# board_schematic_v2.net
KiCad netlist of a schematic drawn in EAGLE
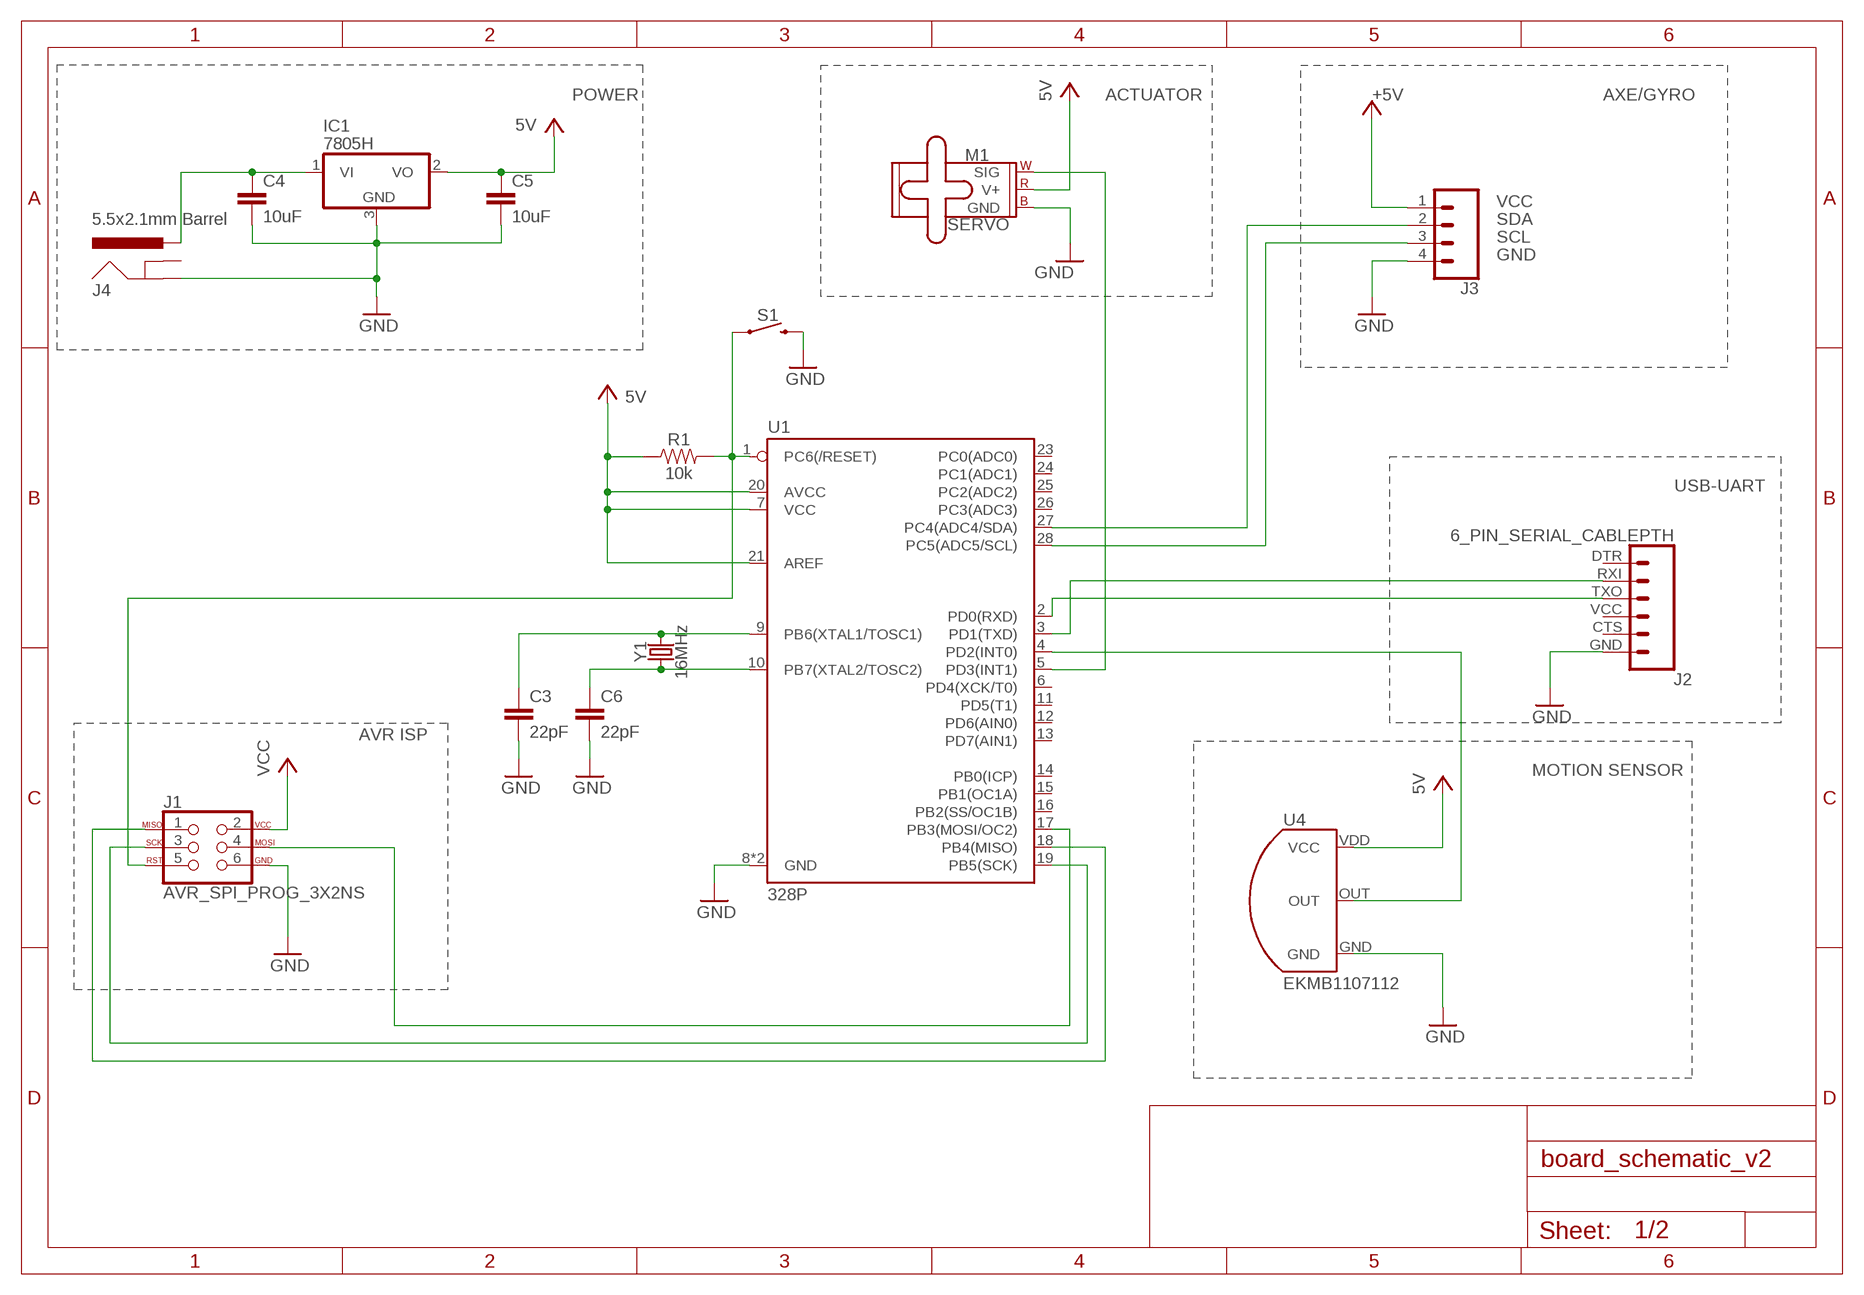
[diagram p0: schematic, sheet 1]

(export (version "E")
  (design (tool "Eeschema 10.0.6"))
  (components
    (comp (ref "C3")
      (value "22pF")
      (footprint "eagle-import:0402-TIGHT")
      (libsource (lib "eagle-import") (part "22PF-0402T-16V-10%"))
    )
    (comp (ref "C4")
      (value "10uF")
      (footprint "eagle-import:0402-TIGHT")
      (libsource (lib "eagle-import") (part "10UF-0402T-6.3V-20%"))
    )
    (comp (ref "C5")
      (value "10uF")
      (footprint "eagle-import:0402-TIGHT")
      (libsource (lib "eagle-import") (part "10UF-0402T-6.3V-20%"))
    )
    (comp (ref "C6")
      (value "22pF")
      (footprint "eagle-import:0402-TIGHT")
      (libsource (lib "eagle-import") (part "22PF-0402T-16V-10%"))
    )
    (comp (ref "IC1")
      (value "7805H")
      (footprint "eagle-import:TO39")
      (libsource (lib "eagle-import") (part "78H05"))
    )
    (comp (ref "J1")
      (value "AVR_SPI_PROG_3X2NS")
      (footprint "eagle-import:2X3-NS")
      (libsource (lib "eagle-import") (part "AVR_SPI_PROG_3X2NS"))
    )
    (comp (ref "J2")
      (value "6_PIN_SERIAL_CABLEPTH")
      (footprint "eagle-import:FTDI_BASIC")
      (libsource (lib "eagle-import") (part "6_PIN_SERIAL_CABLEPTH"))
    )
    (comp (ref "J3")
      (value "CONN_04PTH")
      (footprint "eagle-import:1X04")
      (libsource (lib "eagle-import") (part "CONN_04PTH"))
    )
    (comp (ref "J4")
      (value "5.5x2.1mm Barrel")
      (footprint "eagle-import:POWER_JACK_SMD")
      (libsource (lib "eagle-import") (part "POWER_JACKSMD"))
    )
    (comp (ref "M1")
      (value "SERVO")
      (footprint "eagle-import:1X03")
      (libsource (lib "eagle-import") (part "SERVO"))
    )
    (comp (ref "R1")
      (value "10k")
      (footprint "eagle-import:0402")
      (libsource (lib "eagle-import") (part "10KOHM-0402-1/16W-1%"))
    )
    (comp (ref "S1")
      (value "MOMENTARY-SWITCH-SPST-PTH-6.0MM")
      (footprint "eagle-import:TACTILE_SWITCH_PTH_6.0MM")
      (libsource (lib "eagle-import") (part "MOMENTARY-SWITCH-SPST-PTH-6.0MM"))
    )
    (comp (ref "U1")
      (value "328P")
      (footprint "eagle-import:DIP28")
      (libsource (lib "eagle-import") (part "ATMEGA328P_PDIP"))
    )
    (comp (ref "U4")
      (value "EKMB1107112")
      (footprint "eagle-import:TO-3")
      (libsource (lib "eagle-import") (part "PIR_EKMB1107112"))
    )
    (comp (ref "Y1")
      (value "16MHz")
      (footprint "eagle-import:HC49US")
      (libsource (lib "eagle-import") (part "CRYSTAL-16MHZPTH-HC49US"))
    )
  )
  (nets
    (net (code "1") (name "GND") (class "Default")
      (node (ref "C3") (pin "2") (pinfunction "2_2") (pintype "passive"))
      (node (ref "C4") (pin "2") (pinfunction "2_2") (pintype "passive"))
      (node (ref "C5") (pin "2") (pinfunction "2_2") (pintype "passive"))
      (node (ref "C6") (pin "2") (pinfunction "2_2") (pintype "passive"))
      (node (ref "IC1") (pin "3") (pinfunction "GND_3") (pintype "passive"))
      (node (ref "J1") (pin "6") (pinfunction "6_6") (pintype "passive"))
      (node (ref "J2") (pin "GND") (pinfunction "6_GND") (pintype "passive"))
      (node (ref "J3") (pin "4") (pinfunction "4_4") (pintype "passive"))
      (node (ref "J4") (pin "P$4") (pinfunction "GND_P$4") (pintype "bidirectional"))
      (node (ref "M1") (pin "3") (pinfunction "GND_3") (pintype "bidirectional"))
      (node (ref "S1") (pin "3") (pinfunction "2_3") (pintype "passive"))
      (node (ref "U1") (pin "22") (pinfunction "GND_22") (pintype "bidirectional"))
      (node (ref "U1") (pin "8") (pinfunction "GND_8") (pintype "bidirectional"))
      (node (ref "U4") (pin "GND") (pinfunction "GND_GND") (pintype "bidirectional"))
    )
    (net (code "2") (name "Net-(IC1-VI)") (class "Default")
      (node (ref "C4") (pin "1") (pinfunction "1_1") (pintype "passive"))
      (node (ref "IC1") (pin "1") (pinfunction "VI_1") (pintype "input"))
      (node (ref "J4") (pin "VIN0") (pinfunction "PWR_VIN0") (pintype "bidirectional"))
    )
    (net (code "3") (name "Net-(J2-2)") (class "Default")
      (node (ref "J2") (pin "RXI") (pinfunction "2_RXI") (pintype "passive"))
      (node (ref "U1") (pin "3") (pinfunction "PD1(TXD)_3") (pintype "bidirectional"))
    )
    (net (code "4") (name "Net-(J2-3)") (class "Default")
      (node (ref "J2") (pin "TXO") (pinfunction "3_TXO") (pintype "passive"))
      (node (ref "U1") (pin "2") (pinfunction "PD0(RXD)_2") (pintype "bidirectional"))
    )
    (net (code "5") (name "Net-(M1-SIG)") (class "Default")
      (node (ref "M1") (pin "1") (pinfunction "SIG_1") (pintype "bidirectional"))
      (node (ref "U1") (pin "5") (pinfunction "PD3(INT1)_5") (pintype "bidirectional"))
    )
    (net (code "6") (name "Net-(U1-PB3(MOSI{slash}OC2))") (class "Default")
      (node (ref "J1") (pin "4") (pinfunction "4_4") (pintype "passive"))
      (node (ref "U1") (pin "17") (pinfunction "PB3(MOSI/OC2)_17") (pintype "bidirectional"))
    )
    (net (code "7") (name "Net-(U1-PB4(MISO))") (class "Default")
      (node (ref "J1") (pin "1") (pinfunction "1_1") (pintype "passive"))
      (node (ref "U1") (pin "18") (pinfunction "PB4(MISO)_18") (pintype "bidirectional"))
    )
    (net (code "8") (name "Net-(U1-PB5(SCK))") (class "Default")
      (node (ref "J1") (pin "3") (pinfunction "3_3") (pintype "passive"))
      (node (ref "U1") (pin "19") (pinfunction "PB5(SCK)_19") (pintype "bidirectional"))
    )
    (net (code "9") (name "Net-(U1-PB6(XTAL1{slash}TOSC1))") (class "Default")
      (node (ref "C3") (pin "1") (pinfunction "1_1") (pintype "passive"))
      (node (ref "U1") (pin "9") (pinfunction "PB6(XTAL1/TOSC1)_9") (pintype "bidirectional"))
      (node (ref "Y1") (pin "2") (pinfunction "2_2") (pintype "passive"))
    )
    (net (code "10") (name "Net-(U1-PB7(XTAL2{slash}TOSC2))") (class "Default")
      (node (ref "C6") (pin "1") (pinfunction "1_1") (pintype "passive"))
      (node (ref "U1") (pin "10") (pinfunction "PB7(XTAL2/TOSC2)_10") (pintype "bidirectional"))
      (node (ref "Y1") (pin "1") (pinfunction "1_1") (pintype "passive"))
    )
    (net (code "11") (name "Net-(U1-PC4(ADC4{slash}SDA))") (class "Default")
      (node (ref "J3") (pin "2") (pinfunction "2_2") (pintype "passive"))
      (node (ref "U1") (pin "27") (pinfunction "PC4(ADC4/SDA)_27") (pintype "bidirectional"))
    )
    (net (code "12") (name "Net-(U1-PC5(ADC5{slash}SCL))") (class "Default")
      (node (ref "J3") (pin "3") (pinfunction "3_3") (pintype "passive"))
      (node (ref "U1") (pin "28") (pinfunction "PC5(ADC5/SCL)_28") (pintype "bidirectional"))
    )
    (net (code "13") (name "Net-(U1-PC6({slash}RESET))") (class "Default")
      (node (ref "J1") (pin "5") (pinfunction "5_5") (pintype "passive"))
      (node (ref "R1") (pin "2") (pinfunction "2_2") (pintype "passive"))
      (node (ref "S1") (pin "1") (pinfunction "1_1") (pintype "passive"))
      (node (ref "U1") (pin "1") (pinfunction "PC6(/RESET)_1") (pintype "bidirectional"))
    )
    (net (code "14") (name "Net-(U1-PD2(INT0))") (class "Default")
      (node (ref "U1") (pin "4") (pinfunction "PD2(INT0)_4") (pintype "bidirectional"))
      (node (ref "U4") (pin "OUT") (pinfunction "OUT_OUT") (pintype "bidirectional"))
    )
    (net (code "15") (name "VCC") (class "Default")
      (node (ref "C5") (pin "1") (pinfunction "1_1") (pintype "passive"))
      (node (ref "IC1") (pin "2") (pinfunction "VO_2") (pintype "passive"))
      (node (ref "J1") (pin "2") (pinfunction "2_2") (pintype "passive"))
      (node (ref "J3") (pin "1") (pinfunction "1_1") (pintype "passive"))
      (node (ref "M1") (pin "2") (pinfunction "V+_2") (pintype "bidirectional"))
      (node (ref "R1") (pin "1") (pinfunction "1_1") (pintype "passive"))
      (node (ref "U1") (pin "20") (pinfunction "AVCC_20") (pintype "bidirectional"))
      (node (ref "U1") (pin "21") (pinfunction "AREF_21") (pintype "bidirectional"))
      (node (ref "U1") (pin "7") (pinfunction "VCC_7") (pintype "bidirectional"))
      (node (ref "U4") (pin "VDD") (pinfunction "VCC_VDD") (pintype "bidirectional"))
    )
    (net (code "16") (name "unconnected-(J2-1-PadDTR)") (class "Default")
      (node (ref "J2") (pin "DTR") (pinfunction "1_DTR") (pintype "passive"))
    )
    (net (code "17") (name "unconnected-(J2-4-PadVCC)") (class "Default")
      (node (ref "J2") (pin "VCC") (pinfunction "4_VCC") (pintype "passive"))
    )
    (net (code "18") (name "unconnected-(J2-5-PadCTS)") (class "Default")
      (node (ref "J2") (pin "CTS") (pinfunction "5_CTS") (pintype "passive"))
    )
    (net (code "19") (name "unconnected-(J4-GNDBREAK-PadGND)") (class "Default")
      (node (ref "J4") (pin "GND") (pinfunction "GNDBREAK_GND") (pintype "bidirectional"))
    )
    (net (code "20") (name "unconnected-(U1-PB0(ICP)-Pad14)") (class "Default")
      (node (ref "U1") (pin "14") (pinfunction "PB0(ICP)_14") (pintype "bidirectional"))
    )
    (net (code "21") (name "unconnected-(U1-PB1(OC1A)-Pad15)") (class "Default")
      (node (ref "U1") (pin "15") (pinfunction "PB1(OC1A)_15") (pintype "bidirectional"))
    )
    (net (code "22") (name "unconnected-(U1-PB2(SS{slash}OC1B)-Pad16)") (class "Default")
      (node (ref "U1") (pin "16") (pinfunction "PB2(SS/OC1B)_16") (pintype "bidirectional"))
    )
    (net (code "23") (name "unconnected-(U1-PC0(ADC0)-Pad23)") (class "Default")
      (node (ref "U1") (pin "23") (pinfunction "PC0(ADC0)_23") (pintype "bidirectional"))
    )
    (net (code "24") (name "unconnected-(U1-PC1(ADC1)-Pad24)") (class "Default")
      (node (ref "U1") (pin "24") (pinfunction "PC1(ADC1)_24") (pintype "bidirectional"))
    )
    (net (code "25") (name "unconnected-(U1-PC2(ADC2)-Pad25)") (class "Default")
      (node (ref "U1") (pin "25") (pinfunction "PC2(ADC2)_25") (pintype "bidirectional"))
    )
    (net (code "26") (name "unconnected-(U1-PC3(ADC3)-Pad26)") (class "Default")
      (node (ref "U1") (pin "26") (pinfunction "PC3(ADC3)_26") (pintype "bidirectional"))
    )
    (net (code "27") (name "unconnected-(U1-PD4(XCK{slash}T0)-Pad6)") (class "Default")
      (node (ref "U1") (pin "6") (pinfunction "PD4(XCK/T0)_6") (pintype "bidirectional"))
    )
    (net (code "28") (name "unconnected-(U1-PD5(T1)-Pad11)") (class "Default")
      (node (ref "U1") (pin "11") (pinfunction "PD5(T1)_11") (pintype "bidirectional"))
    )
    (net (code "29") (name "unconnected-(U1-PD6(AIN0)-Pad12)") (class "Default")
      (node (ref "U1") (pin "12") (pinfunction "PD6(AIN0)_12") (pintype "bidirectional"))
    )
    (net (code "30") (name "unconnected-(U1-PD7(AIN1)-Pad13)") (class "Default")
      (node (ref "U1") (pin "13") (pinfunction "PD7(AIN1)_13") (pintype "bidirectional"))
    )
  )
)
